# Power.net
KiCad netlist of a schematic drawn in Altium Designer
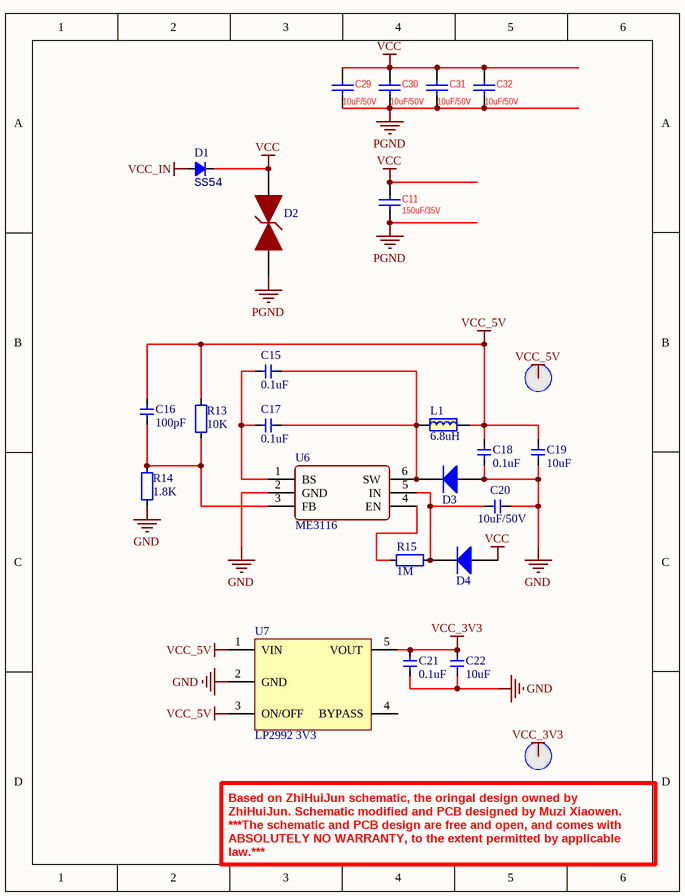
[diagram p0: Power.SchDoc]

(export (version "E")
  (design (tool "Eeschema 10.0.6"))
  (components
    (comp (ref "C11")
      (value "150uF/35V")
      (footprint "CAP-SMD_BD8.0-L8.3-W8.3-LS9.3-FD")
      (description "Capacitor, chip, ceramic")
      (fields (field (name "Comment") "220uF/25V"))
      (libsource (lib "OAKUSBFXS") (part "CAP"))
    )
    (comp (ref "C15")
      (value "0.1uF")
      (footprint "motor42-lib:CAP_0402")
      (description "Capacitor")
      (libsource (lib "MyPcbLib") (part "电容-0402"))
    )
    (comp (ref "C16")
      (value "100pF")
      (footprint "CAP_0402")
      (description "Capacitor")
      (libsource (lib "MyPcbLib") (part "电容-0402"))
    )
    (comp (ref "C17")
      (value "0.1uF")
      (footprint "motor42-lib:CAP_0402")
      (description "Capacitor")
      (libsource (lib "MyPcbLib") (part "电容-0402"))
    )
    (comp (ref "C18")
      (value "0.1uF")
      (footprint "motor42-lib:CAP_0402")
      (description "Capacitor")
      (libsource (lib "MyPcbLib") (part "电容-0402"))
    )
    (comp (ref "C19")
      (value "10uF")
      (footprint "CAP_0402")
      (description "Capacitor")
      (libsource (lib "MyPcbLib") (part "电容-0402"))
    )
    (comp (ref "C20")
      (value "10uF/50V")
      (footprint "1206-CAP")
      (description "Capacitor")
      (libsource (lib "MyPcbLib") (part "电容-0402"))
    )
    (comp (ref "C21")
      (value "0.1uF")
      (footprint "motor42-lib:CAP_0402")
      (description "Capacitor")
      (libsource (lib "MyPcbLib") (part "电容-0402"))
    )
    (comp (ref "C22")
      (value "10uF")
      (footprint "CAP_0402")
      (description "Capacitor")
      (libsource (lib "MyPcbLib") (part "电容-0402"))
    )
    (comp (ref "C29")
      (value "10uF/50V")
      (footprint "1206-CAP")
      (description "Capacitor, chip, ceramic")
      (libsource (lib "OAKUSBFXS") (part "CAP"))
    )
    (comp (ref "C30")
      (value "10uF/50V")
      (footprint "1206-CAP")
      (description "Capacitor, chip, ceramic")
      (libsource (lib "OAKUSBFXS") (part "CAP"))
    )
    (comp (ref "C31")
      (value "10uF/50V")
      (footprint "1206-CAP")
      (description "Capacitor, chip, ceramic")
      (libsource (lib "OAKUSBFXS") (part "CAP"))
    )
    (comp (ref "C32")
      (value "10uF/50V")
      (footprint "1206-CAP")
      (description "Capacitor, chip, ceramic")
      (libsource (lib "OAKUSBFXS") (part "CAP"))
    )
    (comp (ref "D1")
      (value "SS54")
      (footprint "DO-214AC")
      (description "Diode")
      (libsource (lib "KitSprout") (part "Diode_SMA"))
    )
    (comp (ref "D2")
      (value "SMBJ28CA")
      (footprint "SMBJ-CA_MFG")
      (libsource (lib "MyPcbLib") (part "SMBJ28CA"))
    )
    (comp (ref "D3")
      (value "二极管-5819W")
      (footprint "SOD-323")
      (description "40V")
      (libsource (lib "MyPcbLib") (part "二极管-5819W"))
    )
    (comp (ref "D4")
      (value "二极管-5819W")
      (footprint "SOD-323")
      (description "40V")
      (libsource (lib "MyPcbLib") (part "二极管-5819W"))
    )
    (comp (ref "L1") (value "6.8uH") (footprint "IND-201612") (libsource (lib "MyPcbLib") (part "电感-201612")))
    (comp (ref "R13")
      (value "10K")
      (footprint "RES_0402")
      (description "Resistor")
      (libsource (lib "MyPcbLib") (part "电阻-0402"))
    )
    (comp (ref "R14")
      (value "1.8K")
      (footprint "RES_0402")
      (description "Resistor")
      (libsource (lib "MyPcbLib") (part "电阻-0402"))
    )
    (comp (ref "R15")
      (value "1M")
      (footprint "RES_0402")
      (description "Resistor")
      (libsource (lib "") (part "电阻-0402_1"))
    )
    (comp (ref "T1") (value "测试点") (footprint "TEST_PT") (libsource (lib "MyPcbLib") (part "测试点")))
    (comp (ref "T2") (value "测试点") (footprint "TEST_PT") (libsource (lib "MyPcbLib") (part "测试点")))
    (comp (ref "U6")
      (value "ME3116")
      (footprint "SOT23-6")
      (description "DC-DC")
      (libsource (lib "MyPcbLib") (part "ME3116"))
    )
    (comp (ref "U7")
      (value "LP2992 3V3")
      (footprint "SOT23-5")
      (description "LDO")
      (libsource (lib "MyPcbLib") (part "LP2992"))
    )
  )
  (nets
    (net (code "1") (name "GND") (class "Default")
      (node (ref "C18") (pin "1") (pinfunction "1_1") (pintype "passive"))
      (node (ref "C19") (pin "1") (pinfunction "1_1") (pintype "passive"))
      (node (ref "C20") (pin "1") (pinfunction "1_1") (pintype "passive"))
      (node (ref "C21") (pin "1") (pinfunction "1_1") (pintype "passive"))
      (node (ref "C22") (pin "1") (pinfunction "1_1") (pintype "passive"))
      (node (ref "D3") (pin "1") (pinfunction "A_1") (pintype "passive"))
      (node (ref "R14") (pin "1") (pinfunction "1_1") (pintype "passive"))
      (node (ref "U6") (pin "2") (pinfunction "GND_2") (pintype "passive"))
      (node (ref "U7") (pin "2") (pinfunction "GND_2") (pintype "passive"))
    )
    (net (code "2") (name "Net-(D3-K)") (class "Default")
      (node (ref "C15") (pin "1") (pinfunction "1_1") (pintype "passive"))
      (node (ref "C17") (pin "1") (pinfunction "1_1") (pintype "passive"))
      (node (ref "D3") (pin "2") (pinfunction "K_2") (pintype "passive"))
      (node (ref "L1") (pin "1") (pintype "passive"))
      (node (ref "U6") (pin "6") (pinfunction "SW_6") (pintype "passive"))
    )
    (net (code "3") (name "Net-(D4-K)") (class "Default")
      (node (ref "C20") (pin "2") (pinfunction "2_2") (pintype "passive"))
      (node (ref "D4") (pin "2") (pinfunction "K_2") (pintype "passive"))
      (node (ref "R15") (pin "1") (pinfunction "1_1") (pintype "passive"))
      (node (ref "U6") (pin "5") (pinfunction "IN_5") (pintype "passive"))
    )
    (net (code "4") (name "Net-(U6-BS)") (class "Default")
      (node (ref "C15") (pin "2") (pinfunction "2_2") (pintype "passive"))
      (node (ref "C17") (pin "2") (pinfunction "2_2") (pintype "passive"))
      (node (ref "U6") (pin "1") (pinfunction "BS_1") (pintype "passive"))
    )
    (net (code "5") (name "Net-(U6-EN)") (class "Default")
      (node (ref "R15") (pin "2") (pinfunction "2_2") (pintype "passive"))
      (node (ref "U6") (pin "4") (pinfunction "EN_4") (pintype "passive"))
    )
    (net (code "6") (name "Net-(U6-FB)") (class "Default")
      (node (ref "C16") (pin "2") (pinfunction "2_2") (pintype "passive"))
      (node (ref "R13") (pin "1") (pinfunction "1_1") (pintype "passive"))
      (node (ref "R14") (pin "2") (pinfunction "2_2") (pintype "passive"))
      (node (ref "U6") (pin "3") (pinfunction "FB_3") (pintype "passive"))
    )
    (net (code "7") (name "PGND") (class "Default")
      (node (ref "C11") (pin "2") (pinfunction "2_2") (pintype "passive"))
      (node (ref "C29") (pin "2") (pinfunction "2_2") (pintype "passive"))
      (node (ref "C30") (pin "2") (pinfunction "2_2") (pintype "passive"))
      (node (ref "C31") (pin "2") (pinfunction "2_2") (pintype "passive"))
      (node (ref "C32") (pin "2") (pinfunction "2_2") (pintype "passive"))
      (node (ref "D2") (pin "1") (pinfunction "1_1") (pintype "passive"))
    )
    (net (code "8") (name "VCC") (class "Default")
      (node (ref "C11") (pin "1") (pinfunction "1_1") (pintype "passive"))
      (node (ref "C29") (pin "1") (pinfunction "1_1") (pintype "passive"))
      (node (ref "C30") (pin "1") (pinfunction "1_1") (pintype "passive"))
      (node (ref "C31") (pin "1") (pinfunction "1_1") (pintype "passive"))
      (node (ref "C32") (pin "1") (pinfunction "1_1") (pintype "passive"))
      (node (ref "D1") (pin "2") (pinfunction "K_2") (pintype "passive"))
      (node (ref "D2") (pin "2") (pinfunction "2_2") (pintype "passive"))
      (node (ref "D4") (pin "1") (pinfunction "A_1") (pintype "passive"))
    )
    (net (code "9") (name "VCC_3V3") (class "Default")
      (node (ref "C21") (pin "2") (pinfunction "2_2") (pintype "passive"))
      (node (ref "C22") (pin "2") (pinfunction "2_2") (pintype "passive"))
      (node (ref "T2") (pin "0") (pinfunction "0_0") (pintype "passive"))
      (node (ref "U7") (pin "5") (pinfunction "VOUT_5") (pintype "passive"))
    )
    (net (code "10") (name "VCC_5V") (class "Default")
      (node (ref "C16") (pin "1") (pinfunction "1_1") (pintype "passive"))
      (node (ref "C18") (pin "2") (pinfunction "2_2") (pintype "passive"))
      (node (ref "C19") (pin "2") (pinfunction "2_2") (pintype "passive"))
      (node (ref "L1") (pin "2") (pinfunction "2_2") (pintype "passive"))
      (node (ref "R13") (pin "2") (pinfunction "2_2") (pintype "passive"))
      (node (ref "T1") (pin "0") (pinfunction "0_0") (pintype "passive"))
      (node (ref "U7") (pin "1") (pinfunction "VIN_1") (pintype "passive"))
      (node (ref "U7") (pin "3") (pinfunction "ON/OFF_3") (pintype "passive"))
    )
    (net (code "11") (name "VCC_IN") (class "Default")
      (node (ref "D1") (pin "1") (pinfunction "A_1") (pintype "passive"))
    )
    (net (code "12") (name "unconnected-(U7-BYPASS-Pad4)") (class "Default")
      (node (ref "U7") (pin "4") (pinfunction "BYPASS_4") (pintype "passive"))
    )
  )
)
